# Complete.net
KiCad netlist of a schematic drawn in EAGLE
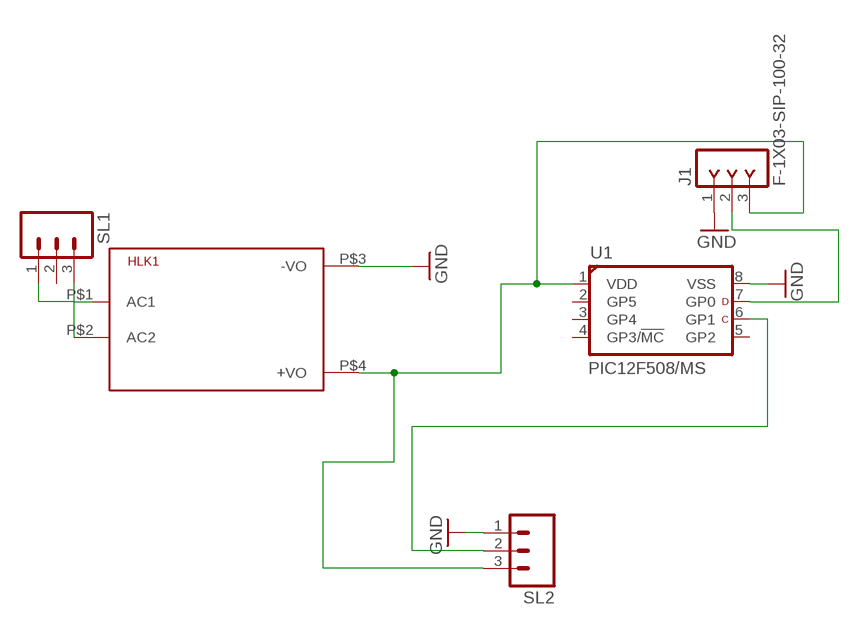
[diagram p0: schematic, sheet 1]

(export (version "E")
  (design (tool "Eeschema 10.0.6"))
  (components
    (comp (ref "HLK1")
      (value "HLK-PM013W")
      (footprint "eagle-import:HLK-PM01")
      (libsource (lib "eagle-import") (part "HLK-PM013W"))
    )
    (comp (ref "J1")
      (value "F-1X03-SIP-100-32")
      (footprint "eagle-import:SIP-100-03-32")
      (libsource (lib "eagle-import") (part "F-1X03-SIP-100-32"))
    )
    (comp (ref "SL1")
      (value "M03")
      (footprint "eagle-import:03P")
      (libsource (lib "eagle-import") (part "M03"))
    )
    (comp (ref "SL2")
      (value "M03")
      (footprint "eagle-import:03P")
      (libsource (lib "eagle-import") (part "M03"))
    )
    (comp (ref "U1")
      (value "PIC12F508/MS")
      (footprint "eagle-import:MSOP8-MS")
      (libsource (lib "eagle-import") (part "PIC12F508/MS"))
    )
  )
  (nets
    (net (code "1") (name "GND") (class "Default")
      (node (ref "HLK1") (pin "P$3") (pinfunction "-VO_P$3") (pintype "bidirectional"))
      (node (ref "J1") (pin "1") (pinfunction "1_1") (pintype "passive"))
      (node (ref "SL2") (pin "1") (pinfunction "1_1") (pintype "passive"))
      (node (ref "U1") (pin "8") (pinfunction "VSS_8") (pintype "passive"))
    )
    (net (code "2") (name "Net-(HLK1-+VO)") (class "Default")
      (node (ref "HLK1") (pin "P$4") (pinfunction "+VO_P$4") (pintype "bidirectional"))
      (node (ref "J1") (pin "3") (pinfunction "3_3") (pintype "passive"))
      (node (ref "SL2") (pin "3") (pinfunction "3_3") (pintype "passive"))
      (node (ref "U1") (pin "1") (pinfunction "VDD_1") (pintype "passive"))
    )
    (net (code "3") (name "Net-(HLK1-AC1)") (class "Default")
      (node (ref "HLK1") (pin "P$1") (pinfunction "AC1_P$1") (pintype "bidirectional"))
      (node (ref "SL1") (pin "1") (pinfunction "1_1") (pintype "passive"))
    )
    (net (code "4") (name "Net-(HLK1-AC2)") (class "Default")
      (node (ref "HLK1") (pin "P$2") (pinfunction "AC2_P$2") (pintype "bidirectional"))
      (node (ref "SL1") (pin "3") (pinfunction "3_3") (pintype "passive"))
    )
    (net (code "5") (name "Net-(U1-GP0)") (class "Default")
      (node (ref "J1") (pin "2") (pinfunction "2_2") (pintype "passive"))
      (node (ref "U1") (pin "7") (pinfunction "GP0_7") (pintype "bidirectional"))
    )
    (net (code "6") (name "Net-(U1-GP1)") (class "Default")
      (node (ref "SL2") (pin "2") (pinfunction "2_2") (pintype "passive"))
      (node (ref "U1") (pin "6") (pinfunction "GP1_6") (pintype "bidirectional"))
    )
    (net (code "7") (name "unconnected-(SL1-Pad2)") (class "Default")
      (node (ref "SL1") (pin "2") (pinfunction "2_2") (pintype "passive"))
    )
    (net (code "8") (name "unconnected-(U1-GP2-Pad5)") (class "Default")
      (node (ref "U1") (pin "5") (pinfunction "GP2_5") (pintype "bidirectional"))
    )
    (net (code "9") (name "unconnected-(U1-GP3{slash}~{MC}-Pad4)") (class "Default")
      (node (ref "U1") (pin "4") (pinfunction "GP3/~{MC}_4") (pintype "bidirectional"))
    )
    (net (code "10") (name "unconnected-(U1-GP4-Pad3)") (class "Default")
      (node (ref "U1") (pin "3") (pinfunction "GP4_3") (pintype "bidirectional"))
    )
    (net (code "11") (name "unconnected-(U1-GP5-Pad2)") (class "Default")
      (node (ref "U1") (pin "2") (pinfunction "GP5_2") (pintype "bidirectional"))
    )
  )
)
